# COMS0004_SwC_Main.net
KiCad netlist of a schematic drawn in Altium Designer
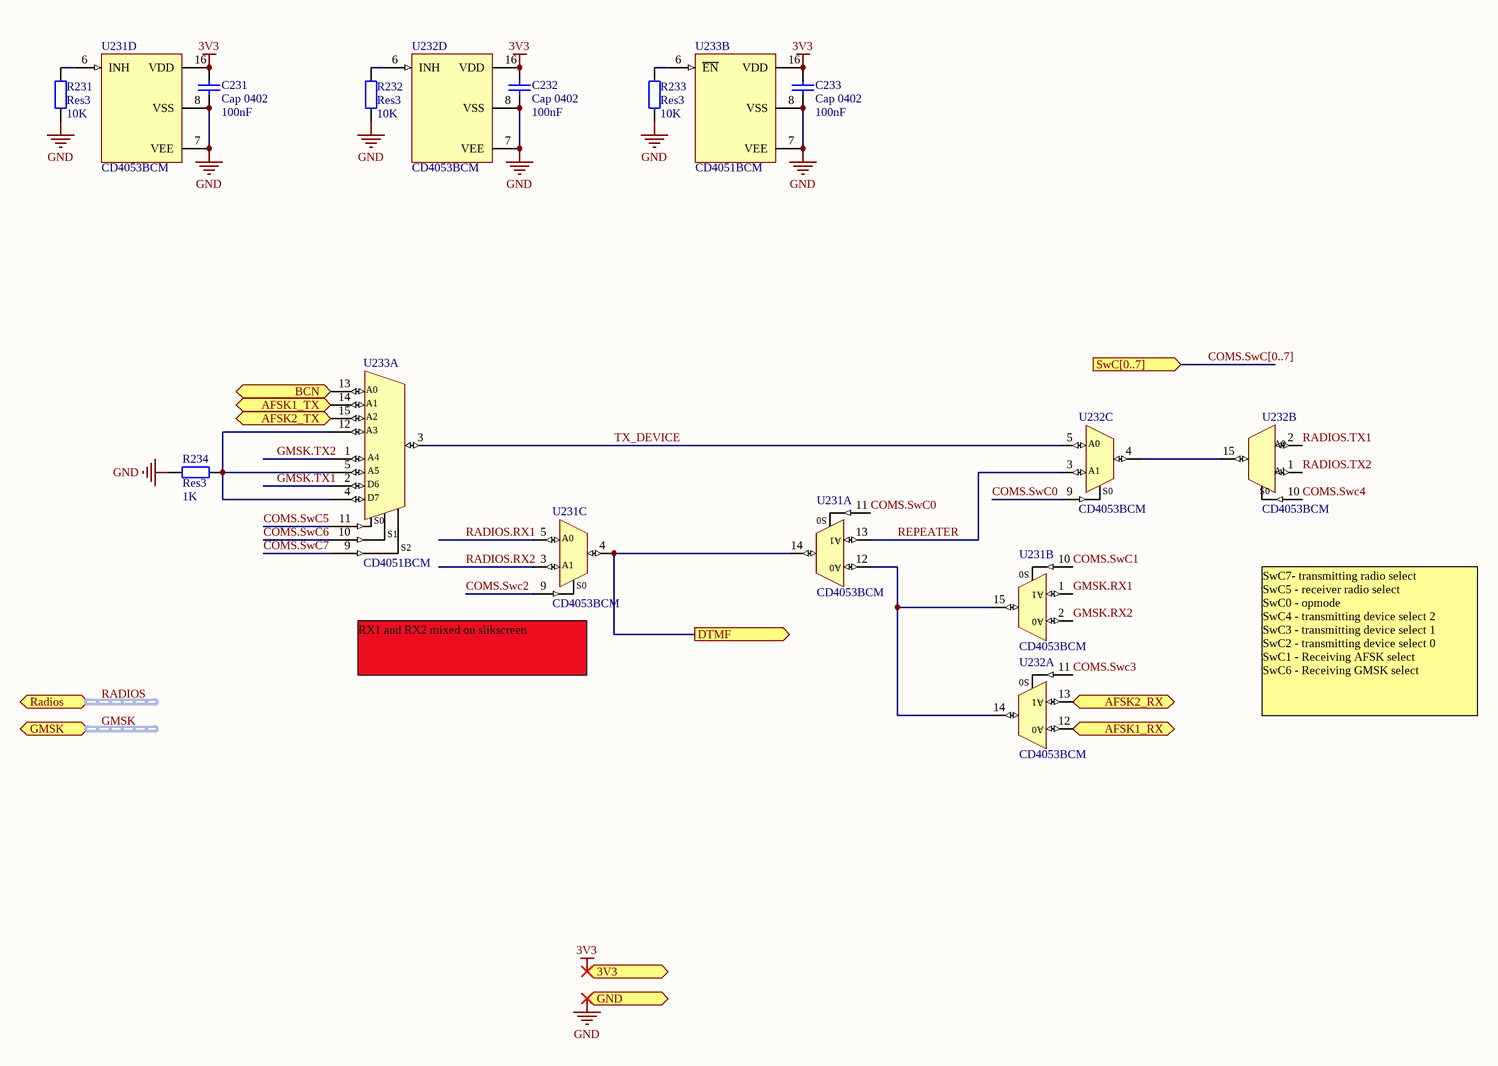
[diagram p0: COMS0004 SwC_Main.SchDoc]

(export (version "E")
  (design (tool "Eeschema 10.0.6"))
  (components
    (comp (ref "C231")
      (value "Cap 0402")
      (footprint "CAPC1005X06L")
      (description "Capacitor")
      (fields (field (name "ALTIUM_VALUE") "100nF") (field (name "PUBLISHER") "Altium Limited"))
      (libsource (lib "CSC") (part "Cap 0402"))
    )
    (comp (ref "C232")
      (value "Cap 0402")
      (footprint "CAPC1005X06L")
      (description "Capacitor")
      (fields (field (name "ALTIUM_VALUE") "100nF") (field (name "PUBLISHER") "Altium Limited"))
      (libsource (lib "CSC") (part "Cap 0402"))
    )
    (comp (ref "C233")
      (value "Cap 0402")
      (footprint "CAPC1005X06L")
      (description "Capacitor")
      (fields (field (name "ALTIUM_VALUE") "100nF") (field (name "PUBLISHER") "Altium Limited"))
      (libsource (lib "CSC") (part "Cap 0402"))
    )
    (comp (ref "R231")
      (value "Res3")
      (footprint "RESC1005X06L")
      (description "Resistor")
      (fields (field (name "ALTIUM_VALUE") "10K") (field (name "PUBLISHER") "Altium Limited"))
      (libsource (lib "") (part "Res3_1"))
    )
    (comp (ref "R232")
      (value "Res3")
      (footprint "RESC1005X06L")
      (description "Resistor")
      (fields (field (name "ALTIUM_VALUE") "10K") (field (name "PUBLISHER") "Altium Limited"))
      (libsource (lib "") (part "Res3_1"))
    )
    (comp (ref "R233")
      (value "Res3")
      (footprint "RESC1005X06L")
      (description "Resistor")
      (fields (field (name "ALTIUM_VALUE") "10K") (field (name "PUBLISHER") "Altium Limited"))
      (libsource (lib "") (part "Res3_1"))
    )
    (comp (ref "R234")
      (value "Res3")
      (footprint "RESC1005X06L")
      (description "Resistor")
      (fields (field (name "ALTIUM_VALUE") "1K") (field (name "PUBLISHER") "Altium Limited"))
      (libsource (lib "CSC") (part "Res3"))
    )
    (comp (ref "U231")
      (value "CD4053BCM")
      (footprint "Comms Board Small Footprints:TSSOP16")
      (description "Triple 2-Channnel Analog Multiplexer/Demutiplexer")
      (libsource (lib "") (part "CD4053BCM_2"))
    )
    (comp (ref "U232")
      (value "CD4053BCM")
      (footprint "Comms Board Small Footprints:TSSOP16")
      (description "Triple 2-Channnel Analog Multiplexer/Demutiplexer")
      (libsource (lib "") (part "CD4053BCM_1"))
    )
    (comp (ref "U233")
      (value "CD4051BCM")
      (footprint "Comms Board Small Footprints:TSSOP16")
      (description "8-Channel Analog Multiplexer/Demultiplexer")
      (libsource (lib "") (part "CD4051BCM_1"))
    )
  )
  (nets
    (net (code "6") (name "/AFSK1_RX") (class "Default")
      (node (ref "U232") (pin "12") (pinfunction "A0_12") (pintype "bidirectional"))
    )
    (net (code "7") (name "/AFSK1_TX") (class "Default")
      (node (ref "U233") (pin "14") (pinfunction "A1_14") (pintype "bidirectional"))
    )
    (net (code "8") (name "/AFSK2_RX") (class "Default")
      (node (ref "U232") (pin "13") (pinfunction "A1_13") (pintype "bidirectional"))
    )
    (net (code "9") (name "/AFSK2_TX") (class "Default")
      (node (ref "U233") (pin "15") (pinfunction "A2_15") (pintype "bidirectional"))
    )
    (net (code "10") (name "/BCN") (class "Default")
      (node (ref "U233") (pin "13") (pinfunction "A0_13") (pintype "bidirectional"))
    )
    (net (code "11") (name "/COMS.SwC0") (class "Default")
      (node (ref "U231") (pin "11") (pinfunction "A_11") (pintype "input"))
      (node (ref "U232") (pin "9") (pinfunction "C_9") (pintype "input"))
    )
    (net (code "12") (name "/COMS.SwC1") (class "Default")
      (node (ref "U231") (pin "10") (pinfunction "B_10") (pintype "input"))
    )
    (net (code "13") (name "/COMS.SwC5") (class "Default")
      (node (ref "U233") (pin "11") (pinfunction "S0_11") (pintype "input"))
    )
    (net (code "14") (name "/COMS.SwC6") (class "Default")
      (node (ref "U233") (pin "10") (pinfunction "S1_10") (pintype "input"))
    )
    (net (code "15") (name "/COMS.SwC7") (class "Default")
      (node (ref "U233") (pin "9") (pinfunction "S2_9") (pintype "input"))
    )
    (net (code "17") (name "/COMS.Swc2") (class "Default")
      (node (ref "U231") (pin "9") (pinfunction "C_9") (pintype "input"))
    )
    (net (code "18") (name "/COMS.Swc3") (class "Default")
      (node (ref "U232") (pin "11") (pinfunction "A_11") (pintype "input"))
    )
    (net (code "19") (name "/COMS.Swc4") (class "Default")
      (node (ref "U232") (pin "10") (pinfunction "B_10") (pintype "input"))
    )
    (net (code "20") (name "/DTMF") (class "Default")
      (node (ref "U231") (pin "14") (pinfunction "A_out_14") (pintype "bidirectional"))
      (node (ref "U231") (pin "4") (pinfunction "c_out_4") (pintype "bidirectional"))
    )
    (net (code "21") (name "/GMSK.RX1") (class "Default")
      (node (ref "U231") (pin "1") (pinfunction "by_1") (pintype "bidirectional"))
    )
    (net (code "22") (name "/GMSK.RX2") (class "Default")
      (node (ref "U231") (pin "2") (pinfunction "bx_2") (pintype "bidirectional"))
    )
    (net (code "23") (name "/GMSK.TX1") (class "Default")
      (node (ref "U233") (pin "2") (pinfunction "A6_2") (pintype "bidirectional"))
    )
    (net (code "24") (name "/GMSK.TX2") (class "Default")
      (node (ref "U233") (pin "1") (pinfunction "A4_1") (pintype "bidirectional"))
    )
    (net (code "25") (name "/RADIOS.RX1") (class "Default")
      (node (ref "U231") (pin "5") (pinfunction "cx_5") (pintype "bidirectional"))
    )
    (net (code "26") (name "/RADIOS.RX2") (class "Default")
      (node (ref "U231") (pin "3") (pinfunction "cy_3") (pintype "bidirectional"))
    )
    (net (code "27") (name "/RADIOS.TX1") (class "Default")
      (node (ref "U232") (pin "2") (pinfunction "bx_2") (pintype "bidirectional"))
    )
    (net (code "28") (name "/RADIOS.TX2") (class "Default")
      (node (ref "U232") (pin "1") (pinfunction "by_1") (pintype "bidirectional"))
    )
    (net (code "29") (name "/REPEATER") (class "Default")
      (node (ref "U231") (pin "13") (pinfunction "A1_13") (pintype "bidirectional"))
      (node (ref "U232") (pin "3") (pinfunction "cy_3") (pintype "bidirectional"))
    )
    (net (code "30") (name "/TX_DEVICE") (class "Default")
      (node (ref "U232") (pin "5") (pinfunction "cx_5") (pintype "bidirectional"))
      (node (ref "U233") (pin "3") (pinfunction "O_3") (pintype "bidirectional"))
    )
    (net (code "33") (name "3V3") (class "Default")
      (node (ref "C231") (pin "2") (pinfunction "2_2") (pintype "passive"))
      (node (ref "C232") (pin "2") (pinfunction "2_2") (pintype "passive"))
      (node (ref "C233") (pin "2") (pinfunction "2_2") (pintype "passive"))
      (node (ref "U231") (pin "16") (pinfunction "VDD_16") (pintype "power_in"))
      (node (ref "U232") (pin "16") (pinfunction "VDD_16") (pintype "power_in"))
      (node (ref "U233") (pin "16") (pinfunction "VDD_16") (pintype "power_in"))
    )
    (net (code "34") (name "GND") (class "Default")
      (node (ref "C231") (pin "1") (pinfunction "1_1") (pintype "passive"))
      (node (ref "C232") (pin "1") (pinfunction "1_1") (pintype "passive"))
      (node (ref "C233") (pin "1") (pinfunction "1_1") (pintype "passive"))
      (node (ref "R231") (pin "2") (pinfunction "2_2") (pintype "passive"))
      (node (ref "R232") (pin "2") (pinfunction "2_2") (pintype "passive"))
      (node (ref "R233") (pin "2") (pinfunction "2_2") (pintype "passive"))
      (node (ref "R234") (pin "1") (pinfunction "1_1") (pintype "passive"))
      (node (ref "U231") (pin "7") (pinfunction "VEE_7") (pintype "power_in"))
      (node (ref "U231") (pin "8") (pinfunction "VSS_8") (pintype "power_in"))
      (node (ref "U232") (pin "7") (pinfunction "VEE_7") (pintype "power_in"))
      (node (ref "U232") (pin "8") (pinfunction "VSS_8") (pintype "power_in"))
      (node (ref "U233") (pin "7") (pinfunction "VEE_7") (pintype "power_in"))
      (node (ref "U233") (pin "8") (pinfunction "VSS_8") (pintype "power_in"))
    )
    (net (code "35") (name "Net-(U231A-A0)") (class "Default")
      (node (ref "U231") (pin "12") (pinfunction "A0_12") (pintype "bidirectional"))
      (node (ref "U231") (pin "15") (pinfunction "b_out_15") (pintype "bidirectional"))
      (node (ref "U232") (pin "14") (pinfunction "A_out_14") (pintype "bidirectional"))
    )
    (net (code "36") (name "Net-(U231D-INH)") (class "Default")
      (node (ref "R231") (pin "1") (pinfunction "1_1") (pintype "passive"))
      (node (ref "U231") (pin "6") (pinfunction "INH_6") (pintype "input"))
    )
    (net (code "37") (name "Net-(U232B-b_out)") (class "Default")
      (node (ref "U232") (pin "15") (pinfunction "b_out_15") (pintype "bidirectional"))
      (node (ref "U232") (pin "4") (pinfunction "c_out_4") (pintype "bidirectional"))
    )
    (net (code "38") (name "Net-(U232D-INH)") (class "Default")
      (node (ref "R232") (pin "1") (pinfunction "1_1") (pintype "passive"))
      (node (ref "U232") (pin "6") (pinfunction "INH_6") (pintype "input"))
    )
    (net (code "39") (name "Net-(U233A-A3)") (class "Default")
      (node (ref "R234") (pin "2") (pinfunction "2_2") (pintype "passive"))
      (node (ref "U233") (pin "12") (pinfunction "A3_12") (pintype "bidirectional"))
      (node (ref "U233") (pin "4") (pinfunction "A7_4") (pintype "bidirectional"))
      (node (ref "U233") (pin "5") (pinfunction "A5_5") (pintype "bidirectional"))
    )
    (net (code "40") (name "Net-(U233B-~{EN})") (class "Default")
      (node (ref "R233") (pin "1") (pinfunction "1_1") (pintype "passive"))
      (node (ref "U233") (pin "6") (pinfunction "~{EN}_6") (pintype "input"))
    )
  )
)
